# INA219_CH2.net
KiCad netlist of a schematic drawn in Altium Designer
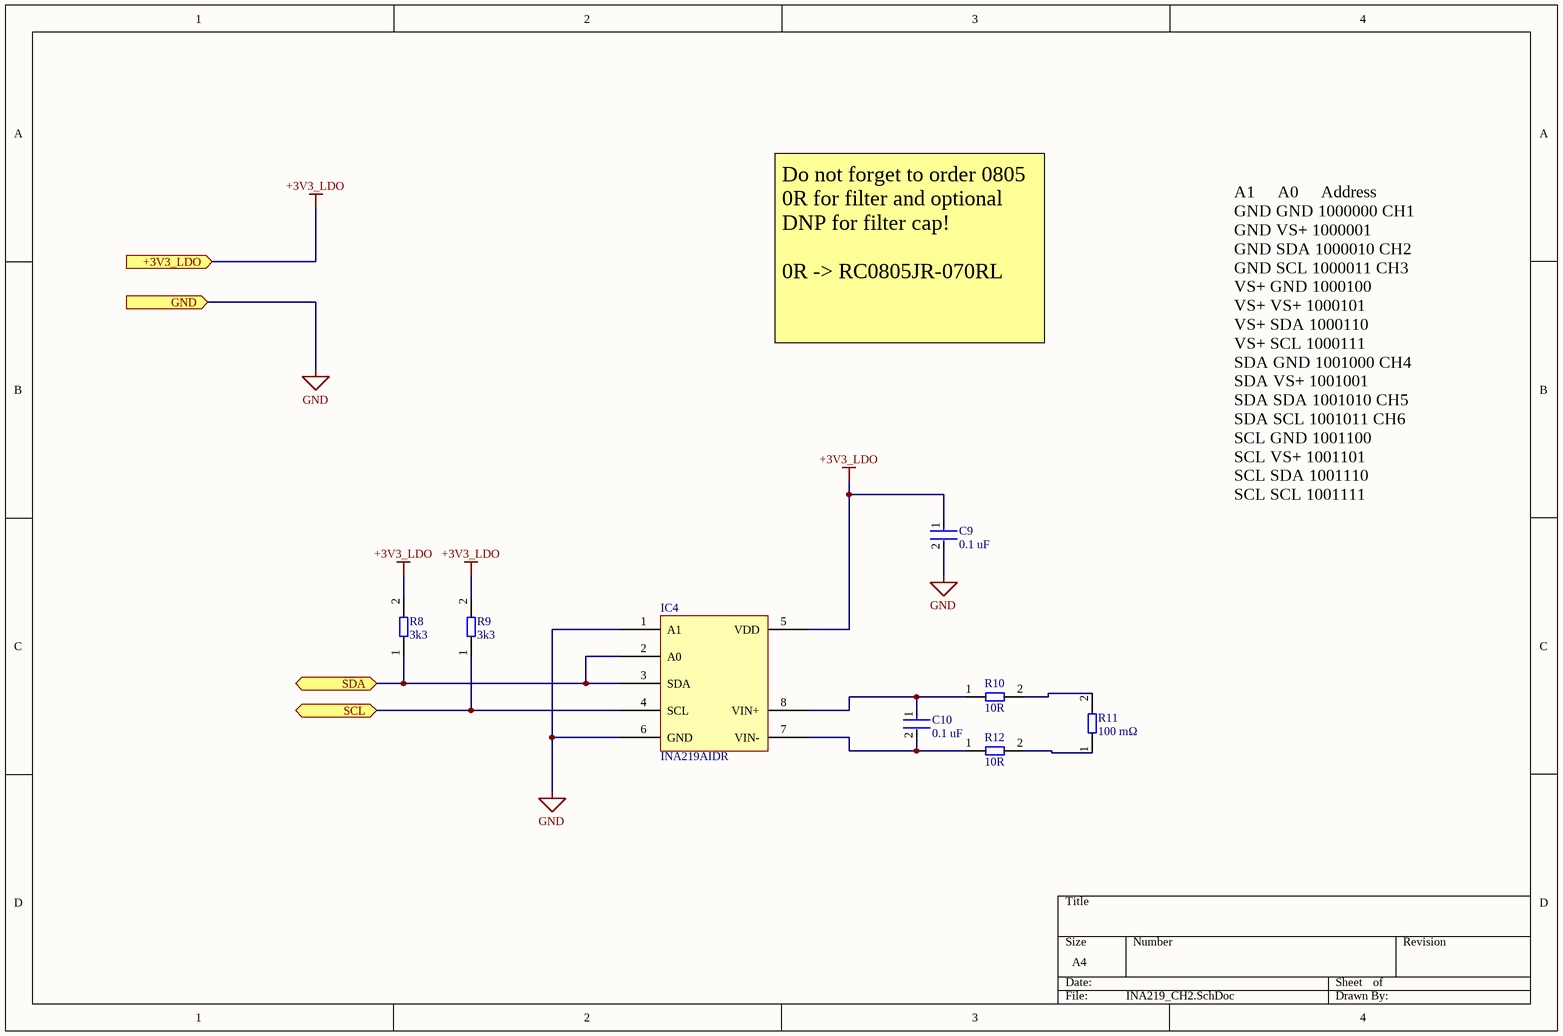
[diagram p0: INA219_CH2.SchDoc]

(export (version "E")
  (design (tool "Eeschema 10.0.6"))
  (components
    (comp (ref "C9")
      (value "0.1 uF")
      (footprint "FP-C0805C-DN-MFG")
      (description "C0805 0.10 μF X7R 30ppm/°C 20.00% 50 V C0805C104M5RAC")
      (fields
        (field (name "MANUFACTURER PART NUMBER") "C0805C104M5RAC")
        (field (name "MANUFACTURER") "KEMET")
      )
      (libsource (lib "Altium Content Vault") (part "b4654b650e69147ec39a6b967a45e02"))
    )
    (comp (ref "C10")
      (value "0.1 uF")
      (footprint "FP-C0805C-DN-MFG")
      (description "C0805 0.10 μF X7R 30ppm/°C 20.00% 50 V C0805C104M5RAC")
      (fields
        (field (name "MANUFACTURER PART NUMBER") "C0805C104M5RAC")
        (field (name "MANUFACTURER") "KEMET")
      )
      (libsource (lib "Altium Content Vault") (part "b4654b650e69147ec39a6b967a45e02"))
    )
    (comp (ref "IC4")
      (value "INA219AIDR")
      (footprint "INA219AIDR")
      (description "Current & Power Monitors & Regulators Zero-Drift,Bi-Dir Crnt/Pwr Monitor")
      (libsource (lib "Callisto Control Board") (part "INA219AIDR"))
    )
    (comp (ref "R8")
      (value "3k3")
      (footprint "0805 Resistor - IPC A")
      (description "Thick Film Resistors - SMD 3.3 kOhms 125 mW 0805 1%\r\nRE0805FRE073K3L")
      (libsource (lib "Callisto Control Board") (part "RE0805FRE073K3L"))
    )
    (comp (ref "R9")
      (value "3k3")
      (footprint "0805 Resistor - IPC A")
      (description "Thick Film Resistors - SMD 3.3 kOhms 125 mW 0805 1%\r\nRE0805FRE073K3L")
      (libsource (lib "Callisto Control Board") (part "RE0805FRE073K3L"))
    )
    (comp (ref "R10")
      (value "10R")
      (footprint "0805 Resistor - IPC A")
      (description "Thick Film Resistors - SMD 10 Ohms 125 mW 0805 1%\r\nRC0805FR-0710RL")
      (libsource (lib "Callisto Control Board") (part "RC0805FR-0710RL"))
    )
    (comp (ref "R11")
      (value "100 mΩ")
      (footprint "PE2512FKM070R1L")
      (description "Current Sense Resistors - SMD 100 mOhms 1 Watt 1 % 75 ppm/C AEC-Q200\r\nPE2512FKM070R1L")
      (libsource (lib "Callisto Control Board") (part "PE2512FKM070R1L"))
    )
    (comp (ref "R12")
      (value "10R")
      (footprint "0805 Resistor - IPC A")
      (description "Thick Film Resistors - SMD 10 Ohms 125 mW 0805 1%\r\nRC0805FR-0710RL")
      (libsource (lib "Callisto Control Board") (part "RC0805FR-0710RL"))
    )
  )
  (nets
    (net (code "1") (name "+3V3_LDO") (class "Default")
      (node (ref "C9") (pin "1") (pinfunction "1_1") (pintype "passive"))
      (node (ref "IC4") (pin "5") (pinfunction "VDD_5") (pintype "passive"))
      (node (ref "R8") (pin "2") (pintype "passive"))
      (node (ref "R9") (pin "2") (pintype "passive"))
    )
    (net (code "2") (name "/SCL") (class "Default")
      (node (ref "IC4") (pin "4") (pinfunction "SCL_4") (pintype "passive"))
      (node (ref "R9") (pin "1") (pintype "passive"))
    )
    (net (code "3") (name "/SDA") (class "Default")
      (node (ref "IC4") (pin "2") (pinfunction "A0_2") (pintype "passive"))
      (node (ref "IC4") (pin "3") (pinfunction "SDA_3") (pintype "passive"))
      (node (ref "R8") (pin "1") (pintype "passive"))
    )
    (net (code "4") (name "GND") (class "Default")
      (node (ref "C9") (pin "2") (pinfunction "2_2") (pintype "passive"))
      (node (ref "IC4") (pin "1") (pinfunction "A1_1") (pintype "passive"))
      (node (ref "IC4") (pin "6") (pinfunction "GND_6") (pintype "passive"))
    )
    (net (code "5") (name "Net-(IC4-VIN+)") (class "Default")
      (node (ref "C10") (pin "1") (pinfunction "1_1") (pintype "passive"))
      (node (ref "IC4") (pin "8") (pinfunction "VIN+_8") (pintype "passive"))
      (node (ref "R10") (pin "1") (pintype "passive"))
    )
    (net (code "6") (name "Net-(IC4-VIN-)") (class "Default")
      (node (ref "C10") (pin "2") (pinfunction "2_2") (pintype "passive"))
      (node (ref "IC4") (pin "7") (pinfunction "VIN-_7") (pintype "passive"))
      (node (ref "R12") (pin "1") (pintype "passive"))
    )
    (net (code "7") (name "Net-(R10-Pad2)") (class "Default")
      (node (ref "R10") (pin "2") (pintype "passive"))
      (node (ref "R11") (pin "2") (pintype "passive"))
    )
    (net (code "8") (name "Net-(R11-Pad1)") (class "Default")
      (node (ref "R11") (pin "1") (pintype "passive"))
      (node (ref "R12") (pin "2") (pintype "passive"))
    )
  )
)
